# Power.net
KiCad netlist of a schematic drawn in Altium Designer
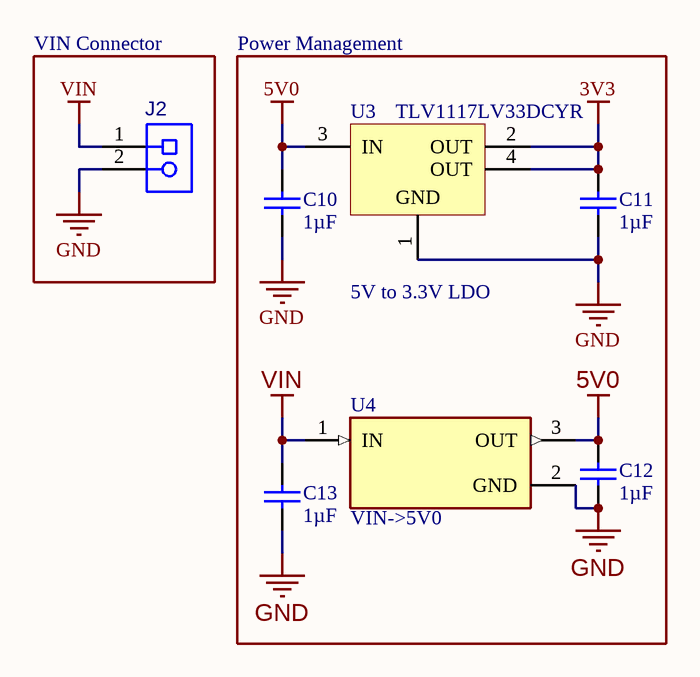
[diagram p0: Power.SchDoc]

(export (version "E")
  (design (tool "Eeschema 10.0.6"))
  (components
    (comp (ref "C10")
      (value "1µF")
      (footprint "CAPC3216X110X50LL20T25")
      (description "Chip Capacitor, 1 uF, +/- 10%, 50 V, -55 to 125 degC, 1206 (3216 Metric), RoHS, Tape and Reel")
      (fields (field (name "MANUFACTURER") "Kemet") (field (name "TOLERANCE") "10%"))
      (libsource (lib "Altium Content Vault") (part "CAP-NP-2"))
    )
    (comp (ref "C11")
      (value "1µF")
      (footprint "CAPC3216X110X50LL20T25")
      (description "Chip Capacitor, 1 uF, +/- 10%, 50 V, -55 to 125 degC, 1206 (3216 Metric), RoHS, Tape and Reel")
      (fields (field (name "MANUFACTURER") "Kemet") (field (name "TOLERANCE") "10%"))
      (libsource (lib "Altium Content Vault") (part "CAP-NP-2"))
    )
    (comp (ref "C12")
      (value "1µF")
      (footprint "CAPC3216X110X50LL20T25")
      (description "Chip Capacitor, 1 uF, +/- 10%, 50 V, -55 to 125 degC, 1206 (3216 Metric), RoHS, Tape and Reel")
      (fields (field (name "MANUFACTURER") "Kemet") (field (name "TOLERANCE") "10%"))
      (libsource (lib "Altium Content Vault") (part "CAP-NP-2"))
    )
    (comp (ref "C13")
      (value "1µF")
      (footprint "CAPC3216X110X50LL20T25")
      (description "Chip Capacitor, 1 uF, +/- 10%, 50 V, -55 to 125 degC, 1206 (3216 Metric), RoHS, Tape and Reel")
      (fields (field (name "MANUFACTURER") "Kemet") (field (name "TOLERANCE") "10%"))
      (libsource (lib "Altium Content Vault") (part "CAP-NP-2"))
    )
    (comp (ref "J2")
      (value "1729128")
      (footprint "PHOE-1729128-2_V")
      (description "PCB Terminal Block, 13.5 A, 400 V, 2-Pin THD, RoHS, Bulk")
      (fields (field (name "MANUFACTURER") "Phoenix Contact"))
      (libsource (lib "Altium Content Vault") (part "CN-2P-F-R2"))
    )
    (comp (ref "U3")
      (value "TLV1117LV33DCYR")
      (footprint "DCY0004A_N")
      (fields (field (name "MANUFACTURER") "Texas Instruments"))
      (libsource (lib "Altium Content Vault") (part "TI-TLV1117LV33DCY4"))
    )
    (comp (ref "U4")
      (value "VIN->5V0")
      (footprint "DPAK229P990X238-4N")
      (description "Linear Voltage Regulator IC 1 Output 1A DPAK")
      (fields (field (name "MP") "MC7805BDTRKG") (field (name "MF") "ON Semiconductor"))
      (libsource (lib "MC7805BDTRKG") (part "MC7805BDTRKG"))
    )
  )
  (nets
    (net (code "1") (name "3V3") (class "Default")
      (node (ref "C11") (pin "2") (pinfunction "2_2") (pintype "passive"))
      (node (ref "U3") (pin "2") (pinfunction "OUT_2") (pintype "power_in"))
      (node (ref "U3") (pin "4") (pinfunction "OUT_4") (pintype "power_in"))
    )
    (net (code "2") (name "5V0") (class "Default")
      (node (ref "C10") (pin "2") (pinfunction "2_2") (pintype "passive"))
      (node (ref "C12") (pin "2") (pinfunction "2_2") (pintype "passive"))
      (node (ref "U3") (pin "3") (pinfunction "IN_3") (pintype "power_in"))
      (node (ref "U4") (pin "3") (pinfunction "OUT_3") (pintype "output"))
    )
    (net (code "3") (name "GND") (class "Default")
      (node (ref "C10") (pin "1") (pinfunction "1_1") (pintype "passive"))
      (node (ref "C11") (pin "1") (pinfunction "1_1") (pintype "passive"))
      (node (ref "C12") (pin "1") (pinfunction "1_1") (pintype "passive"))
      (node (ref "C13") (pin "1") (pinfunction "1_1") (pintype "passive"))
      (node (ref "J2") (pin "2") (pinfunction "2_2") (pintype "passive"))
      (node (ref "U3") (pin "1") (pinfunction "GND_1") (pintype "power_in"))
      (node (ref "U4") (pin "2") (pinfunction "GND_2") (pintype "power_in"))
    )
    (net (code "4") (name "VIN") (class "Default")
      (node (ref "C13") (pin "2") (pinfunction "2_2") (pintype "passive"))
      (node (ref "J2") (pin "1") (pinfunction "1_1") (pintype "passive"))
      (node (ref "U4") (pin "1") (pinfunction "IN_1") (pintype "input"))
    )
  )
)
